# SolenoidTestWiring.net
KiCad netlist of a schematic drawn in EAGLE
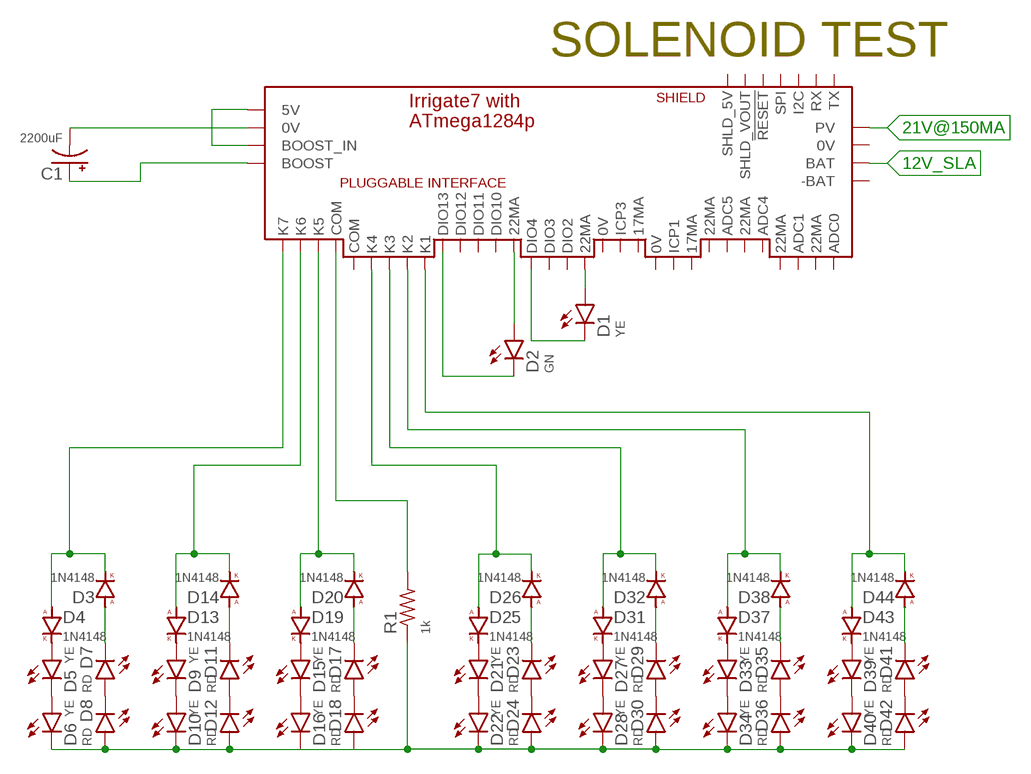
[diagram p0: schematic, sheet 1]

(export (version "E")
  (design (tool "Eeschema 10.0.6"))
  (components
    (comp (ref "C1")
      (value "2200uF")
      (footprint "eagle-import:E7,5-18")
      (libsource (lib "eagle-import") (part "C-AL7.5X18"))
    )
    (comp (ref "D1")
      (value "YE")
      (footprint "eagle-import:LED5MM")
      (libsource (lib "eagle-import") (part "LED5MM"))
    )
    (comp (ref "D2")
      (value "GN")
      (footprint "eagle-import:LED5MM")
      (libsource (lib "eagle-import") (part "LED5MM"))
    )
    (comp (ref "D3")
      (value "1N4148")
      (footprint "eagle-import:DO41.4")
      (libsource (lib "eagle-import") (part "DDO41-10"))
    )
    (comp (ref "D4")
      (value "1N4148")
      (footprint "eagle-import:DO41.4")
      (libsource (lib "eagle-import") (part "DDO41-10"))
    )
    (comp (ref "D5")
      (value "RD")
      (footprint "eagle-import:LED5MM")
      (libsource (lib "eagle-import") (part "LED5MM"))
    )
    (comp (ref "D6")
      (value "RD")
      (footprint "eagle-import:LED5MM")
      (libsource (lib "eagle-import") (part "LED5MM"))
    )
    (comp (ref "D7")
      (value "YE")
      (footprint "eagle-import:LED5MM")
      (libsource (lib "eagle-import") (part "LED5MM"))
    )
    (comp (ref "D8")
      (value "YE")
      (footprint "eagle-import:LED5MM")
      (libsource (lib "eagle-import") (part "LED5MM"))
    )
    (comp (ref "D9")
      (value "RD")
      (footprint "eagle-import:LED5MM")
      (libsource (lib "eagle-import") (part "LED5MM"))
    )
    (comp (ref "D10")
      (value "RD")
      (footprint "eagle-import:LED5MM")
      (libsource (lib "eagle-import") (part "LED5MM"))
    )
    (comp (ref "D11")
      (value "YE")
      (footprint "eagle-import:LED5MM")
      (libsource (lib "eagle-import") (part "LED5MM"))
    )
    (comp (ref "D12")
      (value "YE")
      (footprint "eagle-import:LED5MM")
      (libsource (lib "eagle-import") (part "LED5MM"))
    )
    (comp (ref "D13")
      (value "1N4148")
      (footprint "eagle-import:DO41.4")
      (libsource (lib "eagle-import") (part "DDO41-10"))
    )
    (comp (ref "D14")
      (value "1N4148")
      (footprint "eagle-import:DO41.4")
      (libsource (lib "eagle-import") (part "DDO41-10"))
    )
    (comp (ref "D15")
      (value "RD")
      (footprint "eagle-import:LED5MM")
      (libsource (lib "eagle-import") (part "LED5MM"))
    )
    (comp (ref "D16")
      (value "RD")
      (footprint "eagle-import:LED5MM")
      (libsource (lib "eagle-import") (part "LED5MM"))
    )
    (comp (ref "D17")
      (value "YE")
      (footprint "eagle-import:LED5MM")
      (libsource (lib "eagle-import") (part "LED5MM"))
    )
    (comp (ref "D18")
      (value "YE")
      (footprint "eagle-import:LED5MM")
      (libsource (lib "eagle-import") (part "LED5MM"))
    )
    (comp (ref "D19")
      (value "1N4148")
      (footprint "eagle-import:DO41.4")
      (libsource (lib "eagle-import") (part "DDO41-10"))
    )
    (comp (ref "D20")
      (value "1N4148")
      (footprint "eagle-import:DO41.4")
      (libsource (lib "eagle-import") (part "DDO41-10"))
    )
    (comp (ref "D21")
      (value "RD")
      (footprint "eagle-import:LED5MM")
      (libsource (lib "eagle-import") (part "LED5MM"))
    )
    (comp (ref "D22")
      (value "RD")
      (footprint "eagle-import:LED5MM")
      (libsource (lib "eagle-import") (part "LED5MM"))
    )
    (comp (ref "D23")
      (value "YE")
      (footprint "eagle-import:LED5MM")
      (libsource (lib "eagle-import") (part "LED5MM"))
    )
    (comp (ref "D24")
      (value "YE")
      (footprint "eagle-import:LED5MM")
      (libsource (lib "eagle-import") (part "LED5MM"))
    )
    (comp (ref "D25")
      (value "1N4148")
      (footprint "eagle-import:DO41.4")
      (libsource (lib "eagle-import") (part "DDO41-10"))
    )
    (comp (ref "D26")
      (value "1N4148")
      (footprint "eagle-import:DO41.4")
      (libsource (lib "eagle-import") (part "DDO41-10"))
    )
    (comp (ref "D27")
      (value "RD")
      (footprint "eagle-import:LED5MM")
      (libsource (lib "eagle-import") (part "LED5MM"))
    )
    (comp (ref "D28")
      (value "RD")
      (footprint "eagle-import:LED5MM")
      (libsource (lib "eagle-import") (part "LED5MM"))
    )
    (comp (ref "D29")
      (value "YE")
      (footprint "eagle-import:LED5MM")
      (libsource (lib "eagle-import") (part "LED5MM"))
    )
    (comp (ref "D30")
      (value "YE")
      (footprint "eagle-import:LED5MM")
      (libsource (lib "eagle-import") (part "LED5MM"))
    )
    (comp (ref "D31")
      (value "1N4148")
      (footprint "eagle-import:DO41.4")
      (libsource (lib "eagle-import") (part "DDO41-10"))
    )
    (comp (ref "D32")
      (value "1N4148")
      (footprint "eagle-import:DO41.4")
      (libsource (lib "eagle-import") (part "DDO41-10"))
    )
    (comp (ref "D33")
      (value "RD")
      (footprint "eagle-import:LED5MM")
      (libsource (lib "eagle-import") (part "LED5MM"))
    )
    (comp (ref "D34")
      (value "RD")
      (footprint "eagle-import:LED5MM")
      (libsource (lib "eagle-import") (part "LED5MM"))
    )
    (comp (ref "D35")
      (value "YE")
      (footprint "eagle-import:LED5MM")
      (libsource (lib "eagle-import") (part "LED5MM"))
    )
    (comp (ref "D36")
      (value "YE")
      (footprint "eagle-import:LED5MM")
      (libsource (lib "eagle-import") (part "LED5MM"))
    )
    (comp (ref "D37")
      (value "1N4148")
      (footprint "eagle-import:DO41.4")
      (libsource (lib "eagle-import") (part "DDO41-10"))
    )
    (comp (ref "D38")
      (value "1N4148")
      (footprint "eagle-import:DO41.4")
      (libsource (lib "eagle-import") (part "DDO41-10"))
    )
    (comp (ref "D39")
      (value "RD")
      (footprint "eagle-import:LED5MM")
      (libsource (lib "eagle-import") (part "LED5MM"))
    )
    (comp (ref "D40")
      (value "RD")
      (footprint "eagle-import:LED5MM")
      (libsource (lib "eagle-import") (part "LED5MM"))
    )
    (comp (ref "D41")
      (value "YE")
      (footprint "eagle-import:LED5MM")
      (libsource (lib "eagle-import") (part "LED5MM"))
    )
    (comp (ref "D42")
      (value "YE")
      (footprint "eagle-import:LED5MM")
      (libsource (lib "eagle-import") (part "LED5MM"))
    )
    (comp (ref "D43")
      (value "1N4148")
      (footprint "eagle-import:DO41.4")
      (libsource (lib "eagle-import") (part "DDO41-10"))
    )
    (comp (ref "D44")
      (value "1N4148")
      (footprint "eagle-import:DO41.4")
      (libsource (lib "eagle-import") (part "DDO41-10"))
    )
    (comp (ref "R1")
      (value "1k")
      (footprint "eagle-import:C0805(2012)")
      (libsource (lib "eagle-import") (part "R0805"))
    )
    (comp (ref "U$1")
      (value "IRRIGATE7")
      (footprint "eagle-import:WITH_RPU_NAMES")
      (libsource (lib "eagle-import") (part "IRRIGATE7"))
    )
  )
  (nets
    (net (code "1") (name "12V_SLA") (class "Default")
      (node (ref "U$1") (pin "BAT") (pinfunction "BAT_BAT") (pintype "bidirectional"))
    )
    (net (code "2") (name "21V@150MA") (class "Default")
      (node (ref "U$1") (pin "PV") (pinfunction "PV_PV") (pintype "bidirectional"))
    )
    (net (code "3") (name "Net-(C1-Pad+)") (class "Default")
      (node (ref "C1") (pin "+") (pinfunction "+_+") (pintype "passive"))
      (node (ref "U$1") (pin "BOOST") (pinfunction "BOOST_BOOST") (pintype "bidirectional"))
    )
    (net (code "4") (name "Net-(C1-Pad-)") (class "Default")
      (node (ref "C1") (pin "-") (pinfunction "-_-") (pintype "passive"))
      (node (ref "U$1") (pin "0V") (pinfunction "0V_0V") (pintype "bidirectional"))
    )
    (net (code "5") (name "Net-(D1-PadA)") (class "Default")
      (node (ref "D1") (pin "A") (pinfunction "A_A") (pintype "passive"))
      (node (ref "U$1") (pin "22MA@DIO2") (pinfunction "22MA_22MA@DIO2") (pintype "bidirectional"))
    )
    (net (code "6") (name "Net-(D1-PadK)") (class "Default")
      (node (ref "D1") (pin "K") (pinfunction "K_K") (pintype "passive"))
      (node (ref "U$1") (pin "DIO4") (pinfunction "DIO4_DIO4") (pintype "bidirectional"))
    )
    (net (code "7") (name "Net-(D2-PadA)") (class "Default")
      (node (ref "D2") (pin "A") (pinfunction "A_A") (pintype "passive"))
      (node (ref "U$1") (pin "22MA@DIO10") (pinfunction "22MA_22MA@DIO10") (pintype "bidirectional"))
    )
    (net (code "8") (name "Net-(D2-PadK)") (class "Default")
      (node (ref "D2") (pin "K") (pinfunction "K_K") (pintype "passive"))
      (node (ref "U$1") (pin "DIO13") (pinfunction "DIO13_DIO13") (pintype "bidirectional"))
    )
    (net (code "9") (name "Net-(D3-K)") (class "Default")
      (node (ref "D3") (pin "C") (pinfunction "K_C") (pintype "passive"))
      (node (ref "D4") (pin "A") (pinfunction "A_A") (pintype "passive"))
      (node (ref "U$1") (pin "K7") (pinfunction "K7_K7") (pintype "bidirectional"))
    )
    (net (code "10") (name "Net-(D3-PadA)") (class "Default")
      (node (ref "D3") (pin "A") (pinfunction "A_A") (pintype "passive"))
      (node (ref "D7") (pin "K") (pinfunction "K_K") (pintype "passive"))
    )
    (net (code "11") (name "Net-(D4-K)") (class "Default")
      (node (ref "D4") (pin "C") (pinfunction "K_C") (pintype "passive"))
      (node (ref "D5") (pin "A") (pinfunction "A_A") (pintype "passive"))
    )
    (net (code "12") (name "Net-(D5-PadK)") (class "Default")
      (node (ref "D5") (pin "K") (pinfunction "K_K") (pintype "passive"))
      (node (ref "D6") (pin "A") (pinfunction "A_A") (pintype "passive"))
    )
    (net (code "13") (name "Net-(D7-PadA)") (class "Default")
      (node (ref "D7") (pin "A") (pinfunction "A_A") (pintype "passive"))
      (node (ref "D8") (pin "K") (pinfunction "K_K") (pintype "passive"))
    )
    (net (code "14") (name "Net-(D10-PadA)") (class "Default")
      (node (ref "D10") (pin "A") (pinfunction "A_A") (pintype "passive"))
      (node (ref "D9") (pin "K") (pinfunction "K_K") (pintype "passive"))
    )
    (net (code "15") (name "Net-(D10-PadK)") (class "Default")
      (node (ref "D10") (pin "K") (pinfunction "K_K") (pintype "passive"))
      (node (ref "D12") (pin "A") (pinfunction "A_A") (pintype "passive"))
      (node (ref "D22") (pin "K") (pinfunction "K_K") (pintype "passive"))
      (node (ref "D24") (pin "A") (pinfunction "A_A") (pintype "passive"))
      (node (ref "D28") (pin "K") (pinfunction "K_K") (pintype "passive"))
      (node (ref "D30") (pin "A") (pinfunction "A_A") (pintype "passive"))
      (node (ref "D34") (pin "K") (pinfunction "K_K") (pintype "passive"))
      (node (ref "D36") (pin "A") (pinfunction "A_A") (pintype "passive"))
      (node (ref "D40") (pin "K") (pinfunction "K_K") (pintype "passive"))
      (node (ref "D42") (pin "A") (pinfunction "A_A") (pintype "passive"))
      (node (ref "D6") (pin "K") (pinfunction "K_K") (pintype "passive"))
      (node (ref "D8") (pin "A") (pinfunction "A_A") (pintype "passive"))
      (node (ref "R1") (pin "1") (pinfunction "1_1") (pintype "passive"))
    )
    (net (code "16") (name "Net-(D11-PadA)") (class "Default")
      (node (ref "D11") (pin "A") (pinfunction "A_A") (pintype "passive"))
      (node (ref "D12") (pin "K") (pinfunction "K_K") (pintype "passive"))
    )
    (net (code "17") (name "Net-(D11-PadK)") (class "Default")
      (node (ref "D11") (pin "K") (pinfunction "K_K") (pintype "passive"))
      (node (ref "D14") (pin "A") (pinfunction "A_A") (pintype "passive"))
    )
    (net (code "18") (name "Net-(D13-K)") (class "Default")
      (node (ref "D13") (pin "C") (pinfunction "K_C") (pintype "passive"))
      (node (ref "D9") (pin "A") (pinfunction "A_A") (pintype "passive"))
    )
    (net (code "19") (name "Net-(D14-K)") (class "Default")
      (node (ref "D13") (pin "A") (pinfunction "A_A") (pintype "passive"))
      (node (ref "D14") (pin "C") (pinfunction "K_C") (pintype "passive"))
      (node (ref "U$1") (pin "K6") (pinfunction "K6_K6") (pintype "bidirectional"))
    )
    (net (code "20") (name "Net-(D15-PadK)") (class "Default")
      (node (ref "D15") (pin "K") (pinfunction "K_K") (pintype "passive"))
      (node (ref "D16") (pin "A") (pinfunction "A_A") (pintype "passive"))
    )
    (net (code "21") (name "Net-(D17-PadA)") (class "Default")
      (node (ref "D17") (pin "A") (pinfunction "A_A") (pintype "passive"))
      (node (ref "D18") (pin "K") (pinfunction "K_K") (pintype "passive"))
    )
    (net (code "22") (name "Net-(D17-PadK)") (class "Default")
      (node (ref "D17") (pin "K") (pinfunction "K_K") (pintype "passive"))
      (node (ref "D20") (pin "A") (pinfunction "A_A") (pintype "passive"))
    )
    (net (code "23") (name "Net-(D19-K)") (class "Default")
      (node (ref "D15") (pin "A") (pinfunction "A_A") (pintype "passive"))
      (node (ref "D19") (pin "C") (pinfunction "K_C") (pintype "passive"))
    )
    (net (code "24") (name "Net-(D20-K)") (class "Default")
      (node (ref "D19") (pin "A") (pinfunction "A_A") (pintype "passive"))
      (node (ref "D20") (pin "C") (pinfunction "K_C") (pintype "passive"))
      (node (ref "U$1") (pin "K5") (pinfunction "K5_K5") (pintype "bidirectional"))
    )
    (net (code "25") (name "Net-(D21-PadK)") (class "Default")
      (node (ref "D21") (pin "K") (pinfunction "K_K") (pintype "passive"))
      (node (ref "D22") (pin "A") (pinfunction "A_A") (pintype "passive"))
    )
    (net (code "26") (name "Net-(D23-PadA)") (class "Default")
      (node (ref "D23") (pin "A") (pinfunction "A_A") (pintype "passive"))
      (node (ref "D24") (pin "K") (pinfunction "K_K") (pintype "passive"))
    )
    (net (code "27") (name "Net-(D23-PadK)") (class "Default")
      (node (ref "D23") (pin "K") (pinfunction "K_K") (pintype "passive"))
      (node (ref "D26") (pin "A") (pinfunction "A_A") (pintype "passive"))
    )
    (net (code "28") (name "Net-(D25-K)") (class "Default")
      (node (ref "D21") (pin "A") (pinfunction "A_A") (pintype "passive"))
      (node (ref "D25") (pin "C") (pinfunction "K_C") (pintype "passive"))
    )
    (net (code "29") (name "Net-(D26-K)") (class "Default")
      (node (ref "D25") (pin "A") (pinfunction "A_A") (pintype "passive"))
      (node (ref "D26") (pin "C") (pinfunction "K_C") (pintype "passive"))
      (node (ref "U$1") (pin "K4") (pinfunction "K4_K4") (pintype "bidirectional"))
    )
    (net (code "30") (name "Net-(D27-PadK)") (class "Default")
      (node (ref "D27") (pin "K") (pinfunction "K_K") (pintype "passive"))
      (node (ref "D28") (pin "A") (pinfunction "A_A") (pintype "passive"))
    )
    (net (code "31") (name "Net-(D29-PadA)") (class "Default")
      (node (ref "D29") (pin "A") (pinfunction "A_A") (pintype "passive"))
      (node (ref "D30") (pin "K") (pinfunction "K_K") (pintype "passive"))
    )
    (net (code "32") (name "Net-(D29-PadK)") (class "Default")
      (node (ref "D29") (pin "K") (pinfunction "K_K") (pintype "passive"))
      (node (ref "D32") (pin "A") (pinfunction "A_A") (pintype "passive"))
    )
    (net (code "33") (name "Net-(D31-K)") (class "Default")
      (node (ref "D27") (pin "A") (pinfunction "A_A") (pintype "passive"))
      (node (ref "D31") (pin "C") (pinfunction "K_C") (pintype "passive"))
    )
    (net (code "34") (name "Net-(D32-K)") (class "Default")
      (node (ref "D31") (pin "A") (pinfunction "A_A") (pintype "passive"))
      (node (ref "D32") (pin "C") (pinfunction "K_C") (pintype "passive"))
      (node (ref "U$1") (pin "K3") (pinfunction "K3_K3") (pintype "bidirectional"))
    )
    (net (code "35") (name "Net-(D33-PadK)") (class "Default")
      (node (ref "D33") (pin "K") (pinfunction "K_K") (pintype "passive"))
      (node (ref "D34") (pin "A") (pinfunction "A_A") (pintype "passive"))
    )
    (net (code "36") (name "Net-(D35-PadA)") (class "Default")
      (node (ref "D35") (pin "A") (pinfunction "A_A") (pintype "passive"))
      (node (ref "D36") (pin "K") (pinfunction "K_K") (pintype "passive"))
    )
    (net (code "37") (name "Net-(D35-PadK)") (class "Default")
      (node (ref "D35") (pin "K") (pinfunction "K_K") (pintype "passive"))
      (node (ref "D38") (pin "A") (pinfunction "A_A") (pintype "passive"))
    )
    (net (code "38") (name "Net-(D37-K)") (class "Default")
      (node (ref "D33") (pin "A") (pinfunction "A_A") (pintype "passive"))
      (node (ref "D37") (pin "C") (pinfunction "K_C") (pintype "passive"))
    )
    (net (code "39") (name "Net-(D38-K)") (class "Default")
      (node (ref "D37") (pin "A") (pinfunction "A_A") (pintype "passive"))
      (node (ref "D38") (pin "C") (pinfunction "K_C") (pintype "passive"))
      (node (ref "U$1") (pin "K2") (pinfunction "K2_K2") (pintype "bidirectional"))
    )
    (net (code "40") (name "Net-(D39-PadK)") (class "Default")
      (node (ref "D39") (pin "K") (pinfunction "K_K") (pintype "passive"))
      (node (ref "D40") (pin "A") (pinfunction "A_A") (pintype "passive"))
    )
    (net (code "41") (name "Net-(D41-PadA)") (class "Default")
      (node (ref "D41") (pin "A") (pinfunction "A_A") (pintype "passive"))
      (node (ref "D42") (pin "K") (pinfunction "K_K") (pintype "passive"))
    )
    (net (code "42") (name "Net-(D41-PadK)") (class "Default")
      (node (ref "D41") (pin "K") (pinfunction "K_K") (pintype "passive"))
      (node (ref "D44") (pin "A") (pinfunction "A_A") (pintype "passive"))
    )
    (net (code "43") (name "Net-(D43-K)") (class "Default")
      (node (ref "D39") (pin "A") (pinfunction "A_A") (pintype "passive"))
      (node (ref "D43") (pin "C") (pinfunction "K_C") (pintype "passive"))
    )
    (net (code "44") (name "Net-(D44-K)") (class "Default")
      (node (ref "D43") (pin "A") (pinfunction "A_A") (pintype "passive"))
      (node (ref "D44") (pin "C") (pinfunction "K_C") (pintype "passive"))
      (node (ref "U$1") (pin "K1") (pinfunction "K1_K1") (pintype "bidirectional"))
    )
    (net (code "45") (name "Net-(R1-Pad2)") (class "Default")
      (node (ref "R1") (pin "2") (pinfunction "2_2") (pintype "passive"))
      (node (ref "U$1") (pin "COM@K5") (pinfunction "COM_COM@K5") (pintype "bidirectional"))
    )
    (net (code "46") (name "Net-(U$1-Pad5V)") (class "Default")
      (node (ref "U$1") (pin "5V") (pinfunction "5V_5V") (pintype "bidirectional"))
      (node (ref "U$1") (pin "BOOST_IN") (pinfunction "BOOST_IN_BOOST_IN") (pintype "bidirectional"))
    )
    (net (code "47") (name "unconnected-(D16-PadK)") (class "Default")
      (node (ref "D16") (pin "K") (pinfunction "K_K") (pintype "passive"))
    )
    (net (code "48") (name "unconnected-(D18-PadA)") (class "Default")
      (node (ref "D18") (pin "A") (pinfunction "A_A") (pintype "passive"))
    )
    (net (code "49") (name "unconnected-(U$1-0V-Pad0V@ICP1)") (class "Default")
      (node (ref "U$1") (pin "0V@ICP1") (pinfunction "0V_0V@ICP1") (pintype "bidirectional"))
    )
    (net (code "50") (name "unconnected-(U$1-0V-Pad0V@ICP3)") (class "Default")
      (node (ref "U$1") (pin "0V@ICP3") (pinfunction "0V_0V@ICP3") (pintype "bidirectional"))
    )
    (net (code "51") (name "unconnected-(U$1-0V-Pad0V@PV)") (class "Default")
      (node (ref "U$1") (pin "0V@PV") (pinfunction "0V_0V@PV") (pintype "bidirectional"))
    )
    (net (code "52") (name "unconnected-(U$1-17MA-Pad17MA@ICP1)") (class "Default")
      (node (ref "U$1") (pin "17MA@ICP1") (pinfunction "17MA_17MA@ICP1") (pintype "bidirectional"))
    )
    (net (code "53") (name "unconnected-(U$1-17MA-Pad17MA@ICP3)") (class "Default")
      (node (ref "U$1") (pin "17MA@ICP3") (pinfunction "17MA_17MA@ICP3") (pintype "bidirectional"))
    )
    (net (code "54") (name "unconnected-(U$1-22MA-Pad22MA@ADC0)") (class "Default")
      (node (ref "U$1") (pin "22MA@ADC0") (pinfunction "22MA_22MA@ADC0") (pintype "bidirectional"))
    )
    (net (code "55") (name "unconnected-(U$1-22MA-Pad22MA@ADC1)") (class "Default")
      (node (ref "U$1") (pin "22MA@ADC1") (pinfunction "22MA_22MA@ADC1") (pintype "bidirectional"))
    )
    (net (code "56") (name "unconnected-(U$1-22MA-Pad22MA@ADC4)") (class "Default")
      (node (ref "U$1") (pin "22MA@ADC4") (pinfunction "22MA_22MA@ADC4") (pintype "bidirectional"))
    )
    (net (code "57") (name "unconnected-(U$1-22MA-Pad22MA@ADC5)") (class "Default")
      (node (ref "U$1") (pin "22MA@ADC5") (pinfunction "22MA_22MA@ADC5") (pintype "bidirectional"))
    )
    (net (code "58") (name "unconnected-(U$1-COM-PadCOM@K4)") (class "Default")
      (node (ref "U$1") (pin "COM@K4") (pinfunction "COM_COM@K4") (pintype "bidirectional"))
    )
    (net (code "59") (name "unconnected-(U$1-Pad-BAT)") (class "Default")
      (node (ref "U$1") (pin "-BAT") (pinfunction "-BAT_-BAT") (pintype "bidirectional"))
    )
    (net (code "60") (name "unconnected-(U$1-PadADC0)") (class "Default")
      (node (ref "U$1") (pin "ADC0") (pinfunction "ADC0_ADC0") (pintype "bidirectional"))
    )
    (net (code "61") (name "unconnected-(U$1-PadADC1)") (class "Default")
      (node (ref "U$1") (pin "ADC1") (pinfunction "ADC1_ADC1") (pintype "bidirectional"))
    )
    (net (code "62") (name "unconnected-(U$1-PadADC4)") (class "Default")
      (node (ref "U$1") (pin "ADC4") (pinfunction "ADC4_ADC4") (pintype "bidirectional"))
    )
    (net (code "63") (name "unconnected-(U$1-PadADC5)") (class "Default")
      (node (ref "U$1") (pin "ADC5") (pinfunction "ADC5_ADC5") (pintype "bidirectional"))
    )
    (net (code "64") (name "unconnected-(U$1-PadDIO2)") (class "Default")
      (node (ref "U$1") (pin "DIO2") (pinfunction "DIO2_DIO2") (pintype "bidirectional"))
    )
    (net (code "65") (name "unconnected-(U$1-PadDIO3)") (class "Default")
      (node (ref "U$1") (pin "DIO3") (pinfunction "DIO3_DIO3") (pintype "bidirectional"))
    )
    (net (code "66") (name "unconnected-(U$1-PadDIO10)") (class "Default")
      (node (ref "U$1") (pin "DIO10") (pinfunction "DIO10_DIO10") (pintype "bidirectional"))
    )
    (net (code "67") (name "unconnected-(U$1-PadDIO11)") (class "Default")
      (node (ref "U$1") (pin "DIO11") (pinfunction "DIO11_DIO11") (pintype "bidirectional"))
    )
    (net (code "68") (name "unconnected-(U$1-PadDIO12)") (class "Default")
      (node (ref "U$1") (pin "DIO12") (pinfunction "DIO12_DIO12") (pintype "bidirectional"))
    )
    (net (code "69") (name "unconnected-(U$1-PadI2C)") (class "Default")
      (node (ref "U$1") (pin "I2C") (pinfunction "I2C_I2C") (pintype "bidirectional"))
    )
    (net (code "70") (name "unconnected-(U$1-PadICP1)") (class "Default")
      (node (ref "U$1") (pin "ICP1") (pinfunction "ICP1_ICP1") (pintype "bidirectional"))
    )
    (net (code "71") (name "unconnected-(U$1-PadICP3)") (class "Default")
      (node (ref "U$1") (pin "ICP3") (pinfunction "ICP3_ICP3") (pintype "bidirectional"))
    )
    (net (code "72") (name "unconnected-(U$1-PadRX)") (class "Default")
      (node (ref "U$1") (pin "RX") (pinfunction "RX_RX") (pintype "bidirectional"))
    )
    (net (code "73") (name "unconnected-(U$1-PadSHLD_5V)") (class "Default")
      (node (ref "U$1") (pin "SHLD_5V") (pinfunction "SHLD_5V_SHLD_5V") (pintype "bidirectional"))
    )
    (net (code "74") (name "unconnected-(U$1-PadSHLD_VOUT)") (class "Default")
      (node (ref "U$1") (pin "SHLD_VOUT") (pinfunction "SHLD_VOUT_SHLD_VOUT") (pintype "bidirectional"))
    )
    (net (code "75") (name "unconnected-(U$1-PadSPI)") (class "Default")
      (node (ref "U$1") (pin "SPI") (pinfunction "SPI_SPI") (pintype "bidirectional"))
    )
    (net (code "76") (name "unconnected-(U$1-PadTX)") (class "Default")
      (node (ref "U$1") (pin "TX") (pinfunction "TX_TX") (pintype "bidirectional"))
    )
    (net (code "77") (name "unconnected-(U$1-~{RESET}-Pad!RESET)") (class "Default")
      (node (ref "U$1") (pin "!RESET") (pinfunction "~{RESET}_!RESET") (pintype "bidirectional"))
    )
  )
)
